# LT1054_Daughterboard.net
KiCad netlist of a schematic drawn in EAGLE
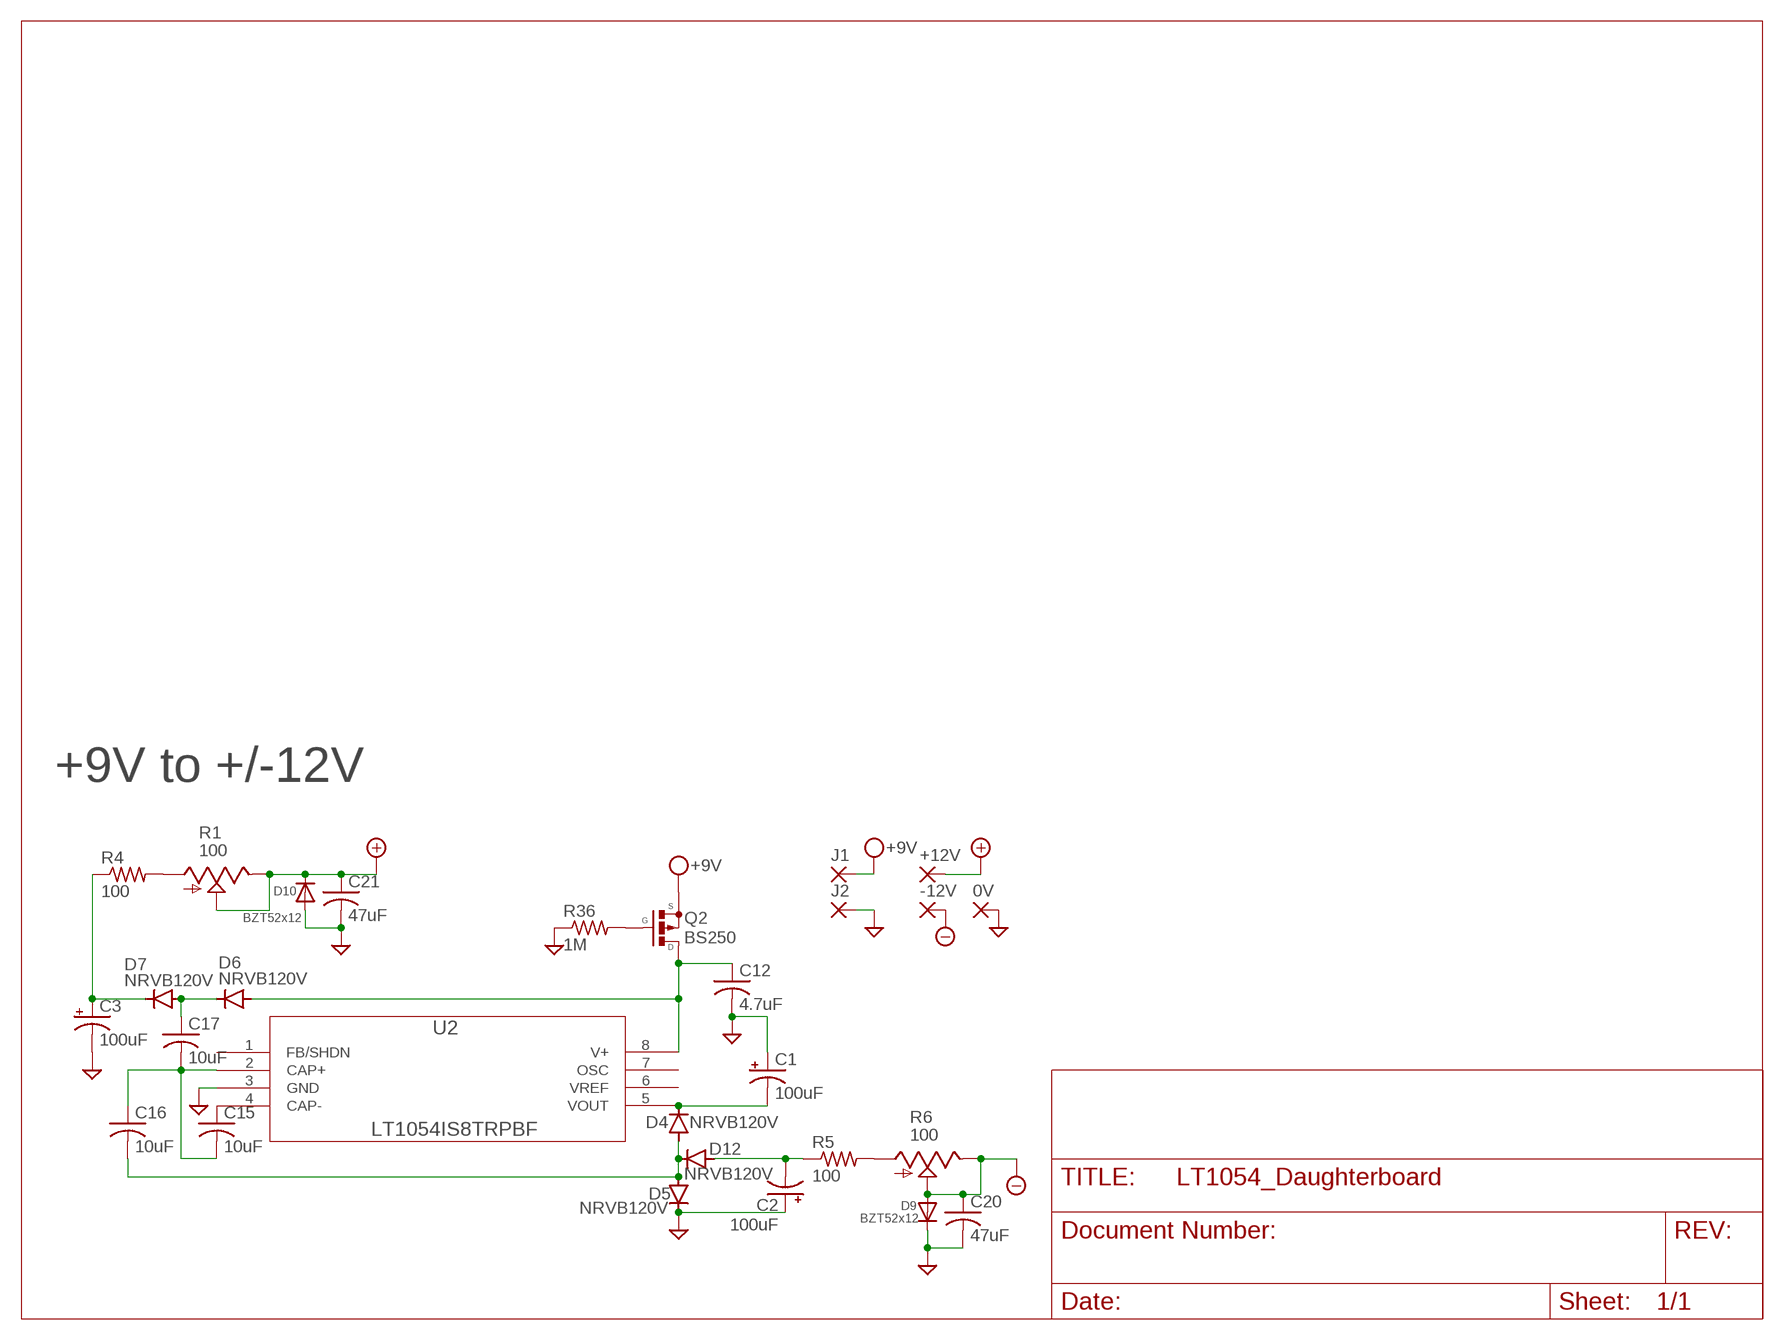
[diagram p0: schematic, sheet 1]

(export (version "E")
  (design (tool "Eeschema 10.0.6"))
  (components
    (comp (ref "+12V")
      (value "SMD2")
      (footprint "eagle-import:SMD1,27-2,54")
      (libsource (lib "eagle-import") (part "SMD2"))
    )
    (comp (ref "-12V")
      (value "SMD2")
      (footprint "eagle-import:SMD1,27-2,54")
      (libsource (lib "eagle-import") (part "SMD2"))
    )
    (comp (ref "0V")
      (value "SMD2")
      (footprint "eagle-import:SMD1,27-2,54")
      (libsource (lib "eagle-import") (part "SMD2"))
    )
    (comp (ref "C1")
      (value "100uF")
      (footprint "eagle-import:E2,5-6E")
      (libsource (lib "eagle-import") (part "CPOL-USE2,5-6E"))
    )
    (comp (ref "C2")
      (value "100uF")
      (footprint "eagle-import:E2,5-6E")
      (libsource (lib "eagle-import") (part "CPOL-USE2,5-6E"))
    )
    (comp (ref "C3")
      (value "100uF")
      (footprint "eagle-import:E2,5-6E")
      (libsource (lib "eagle-import") (part "CPOL-USE2,5-6E"))
    )
    (comp (ref "C12")
      (value "4.7uF")
      (footprint "eagle-import:C0805")
      (libsource (lib "eagle-import") (part "C-USC0805"))
    )
    (comp (ref "C15")
      (value "10uF")
      (footprint "eagle-import:C1206")
      (libsource (lib "eagle-import") (part "C-USC1206"))
    )
    (comp (ref "C16")
      (value "10uF")
      (footprint "eagle-import:C1206")
      (libsource (lib "eagle-import") (part "C-USC1206"))
    )
    (comp (ref "C17")
      (value "10uF")
      (footprint "eagle-import:C1206")
      (libsource (lib "eagle-import") (part "C-USC1206"))
    )
    (comp (ref "C20")
      (value "47uF")
      (footprint "eagle-import:C1206")
      (libsource (lib "eagle-import") (part "C-USC1206"))
    )
    (comp (ref "C21")
      (value "47uF")
      (footprint "eagle-import:C1206")
      (libsource (lib "eagle-import") (part "C-USC1206"))
    )
    (comp (ref "D4")
      (value "NRVB120V")
      (footprint "eagle-import:SOD123")
      (libsource (lib "eagle-import") (part "DIODE-SOD123"))
    )
    (comp (ref "D5")
      (value "NRVB120V")
      (footprint "eagle-import:SOD123")
      (libsource (lib "eagle-import") (part "DIODE-SOD123"))
    )
    (comp (ref "D6")
      (value "NRVB120V")
      (footprint "eagle-import:SOD123")
      (libsource (lib "eagle-import") (part "DIODE-SOD123"))
    )
    (comp (ref "D7")
      (value "NRVB120V")
      (footprint "eagle-import:SOD123")
      (libsource (lib "eagle-import") (part "DIODE-SOD123"))
    )
    (comp (ref "D9")
      (value "BZT52x12")
      (footprint "eagle-import:SOD-123")
      (libsource (lib "eagle-import") (part "DIODESOD-123"))
    )
    (comp (ref "D10")
      (value "BZT52x12")
      (footprint "eagle-import:SOD-123")
      (libsource (lib "eagle-import") (part "DIODESOD-123"))
    )
    (comp (ref "D12")
      (value "NRVB120V")
      (footprint "eagle-import:SOD123")
      (libsource (lib "eagle-import") (part "DIODE-SOD123"))
    )
    (comp (ref "J1")
      (value "SMD2")
      (footprint "eagle-import:SMD1,27-2,54")
      (libsource (lib "eagle-import") (part "SMD2"))
    )
    (comp (ref "J2")
      (value "1,6/0,8")
      (footprint "eagle-import:1,6_0,8")
      (libsource (lib "eagle-import") (part "1,6/0,8"))
    )
    (comp (ref "Q2")
      (value "BS250")
      (footprint "eagle-import:SOT23")
      (libsource (lib "eagle-import") (part "BS250BS250-SOT23-GSD"))
    )
    (comp (ref "R1")
      (value "100")
      (footprint "eagle-import:3223G")
      (libsource (lib "eagle-import") (part "TRIM_US-3223G"))
    )
    (comp (ref "R4")
      (value "100")
      (footprint "eagle-import:R1206")
      (libsource (lib "eagle-import") (part "R-US_R1206"))
    )
    (comp (ref "R5")
      (value "100")
      (footprint "eagle-import:R1206")
      (libsource (lib "eagle-import") (part "R-US_R1206"))
    )
    (comp (ref "R6")
      (value "100")
      (footprint "eagle-import:3223G")
      (libsource (lib "eagle-import") (part "TRIM_US-3223G"))
    )
    (comp (ref "R36")
      (value "1M")
      (footprint "eagle-import:R0805")
      (libsource (lib "eagle-import") (part "R-US_R0805"))
    )
    (comp (ref "U2")
      (value "LT1054IS8TRPBF")
      (footprint "eagle-import:SO-8_S")
      (fields (field (name "MF") "Analog Devices") (field (name "MP") "LT1054IS8#TRPBF"))
      (libsource (lib "eagle-import") (part "LT1054IS8TRPBF"))
    )
  )
  (nets
    (net (code "1") (name "+9V") (class "Default")
      (node (ref "J1") (pin "1") (pinfunction "P_1") (pintype "passive"))
      (node (ref "Q2") (pin "S") (pinfunction "S_S") (pintype "passive"))
    )
    (net (code "2") (name "+12V") (class "Default")
      (node (ref "+12V") (pin "1") (pinfunction "P_1") (pintype "passive"))
      (node (ref "C21") (pin "1") (pinfunction "1_1") (pintype "passive"))
      (node (ref "D10") (pin "C") (pinfunction "C_C") (pintype "passive"))
      (node (ref "R1") (pin "2") (pinfunction "S_2") (pintype "passive"))
      (node (ref "R1") (pin "3") (pinfunction "E_3") (pintype "passive"))
    )
    (net (code "3") (name "-12V") (class "Default")
      (node (ref "-12V") (pin "1") (pinfunction "P_1") (pintype "passive"))
      (node (ref "C20") (pin "1") (pinfunction "1_1") (pintype "passive"))
      (node (ref "D9") (pin "A") (pinfunction "A_A") (pintype "passive"))
      (node (ref "R6") (pin "2") (pinfunction "S_2") (pintype "passive"))
      (node (ref "R6") (pin "3") (pinfunction "E_3") (pintype "passive"))
    )
    (net (code "4") (name "/VREF") (class "Default")
      (node (ref "U2") (pin "6") (pinfunction "VREF_6") (pintype "power_in"))
    )
    (net (code "5") (name "GND") (class "Default")
      (node (ref "0V") (pin "1") (pinfunction "P_1") (pintype "passive"))
      (node (ref "C1") (pin "+") (pinfunction "+_+") (pintype "passive"))
      (node (ref "C12") (pin "2") (pinfunction "2_2") (pintype "passive"))
      (node (ref "C2") (pin "+") (pinfunction "+_+") (pintype "passive"))
      (node (ref "C20") (pin "2") (pinfunction "2_2") (pintype "passive"))
      (node (ref "C21") (pin "2") (pinfunction "2_2") (pintype "passive"))
      (node (ref "C3") (pin "-") (pinfunction "-_-") (pintype "passive"))
      (node (ref "D10") (pin "A") (pinfunction "A_A") (pintype "passive"))
      (node (ref "D5") (pin "C") (pinfunction "C_C") (pintype "passive"))
      (node (ref "D9") (pin "C") (pinfunction "C_C") (pintype "passive"))
      (node (ref "J2") (pin "1") (pinfunction "P_1") (pintype "passive"))
      (node (ref "R36") (pin "1") (pinfunction "1_1") (pintype "passive"))
      (node (ref "U2") (pin "3") (pinfunction "GND_3") (pintype "power_in"))
    )
    (net (code "6") (name "Net-(C2-Pad-)") (class "Default")
      (node (ref "C2") (pin "-") (pinfunction "-_-") (pintype "passive"))
      (node (ref "D12") (pin "A") (pinfunction "A_A") (pintype "passive"))
      (node (ref "R5") (pin "1") (pinfunction "1_1") (pintype "passive"))
    )
    (net (code "7") (name "Net-(C3-Pad+)") (class "Default")
      (node (ref "C3") (pin "+") (pinfunction "+_+") (pintype "passive"))
      (node (ref "D7") (pin "C") (pinfunction "C_C") (pintype "passive"))
      (node (ref "R4") (pin "1") (pinfunction "1_1") (pintype "passive"))
    )
    (net (code "8") (name "Net-(C16-Pad2)") (class "Default")
      (node (ref "C16") (pin "2") (pinfunction "2_2") (pintype "passive"))
      (node (ref "D12") (pin "C") (pinfunction "C_C") (pintype "passive"))
      (node (ref "D4") (pin "A") (pinfunction "A_A") (pintype "passive"))
      (node (ref "D5") (pin "A") (pinfunction "A_A") (pintype "passive"))
    )
    (net (code "9") (name "Net-(C17-Pad1)") (class "Default")
      (node (ref "C17") (pin "1") (pinfunction "1_1") (pintype "passive"))
      (node (ref "D6") (pin "C") (pinfunction "C_C") (pintype "passive"))
      (node (ref "D7") (pin "A") (pinfunction "A_A") (pintype "passive"))
    )
    (net (code "10") (name "Net-(Q2-PadG)") (class "Default")
      (node (ref "Q2") (pin "G") (pinfunction "G_G") (pintype "passive"))
      (node (ref "R36") (pin "2") (pinfunction "2_2") (pintype "passive"))
    )
    (net (code "11") (name "Net-(R1-A)") (class "Default")
      (node (ref "R1") (pin "1") (pinfunction "A_1") (pintype "passive"))
      (node (ref "R4") (pin "2") (pinfunction "2_2") (pintype "passive"))
    )
    (net (code "12") (name "Net-(R6-A)") (class "Default")
      (node (ref "R5") (pin "2") (pinfunction "2_2") (pintype "passive"))
      (node (ref "R6") (pin "1") (pinfunction "A_1") (pintype "passive"))
    )
    (net (code "13") (name "Net-(U2-CAP+)") (class "Default")
      (node (ref "C15") (pin "2") (pinfunction "2_2") (pintype "passive"))
      (node (ref "C16") (pin "1") (pinfunction "1_1") (pintype "passive"))
      (node (ref "C17") (pin "2") (pinfunction "2_2") (pintype "passive"))
      (node (ref "U2") (pin "2") (pinfunction "CAP+_2") (pintype "passive"))
    )
    (net (code "14") (name "Net-(U2-CAP-)") (class "Default")
      (node (ref "C15") (pin "1") (pinfunction "1_1") (pintype "passive"))
      (node (ref "U2") (pin "4") (pinfunction "CAP-_4") (pintype "passive"))
    )
    (net (code "15") (name "Net-(U2-V+)") (class "Default")
      (node (ref "C12") (pin "1") (pinfunction "1_1") (pintype "passive"))
      (node (ref "D6") (pin "A") (pinfunction "A_A") (pintype "passive"))
      (node (ref "Q2") (pin "D") (pinfunction "D_D") (pintype "passive"))
      (node (ref "U2") (pin "8") (pinfunction "V+_8") (pintype "power_in"))
    )
    (net (code "16") (name "Net-(U2-VOUT)") (class "Default")
      (node (ref "C1") (pin "-") (pinfunction "-_-") (pintype "passive"))
      (node (ref "D4") (pin "C") (pinfunction "C_C") (pintype "passive"))
      (node (ref "U2") (pin "5") (pinfunction "VOUT_5") (pintype "output"))
    )
    (net (code "17") (name "unconnected-(U2-FB{slash}SHDN-Pad1)") (class "Default")
      (node (ref "U2") (pin "1") (pinfunction "FB/SHDN_1") (pintype "passive"))
    )
    (net (code "18") (name "unconnected-(U2-OSC-Pad7)") (class "Default")
      (node (ref "U2") (pin "7") (pinfunction "OSC_7") (pintype "passive"))
    )
  )
)
